# RELAIS.net
KiCad netlist of a schematic drawn in Altium Designer
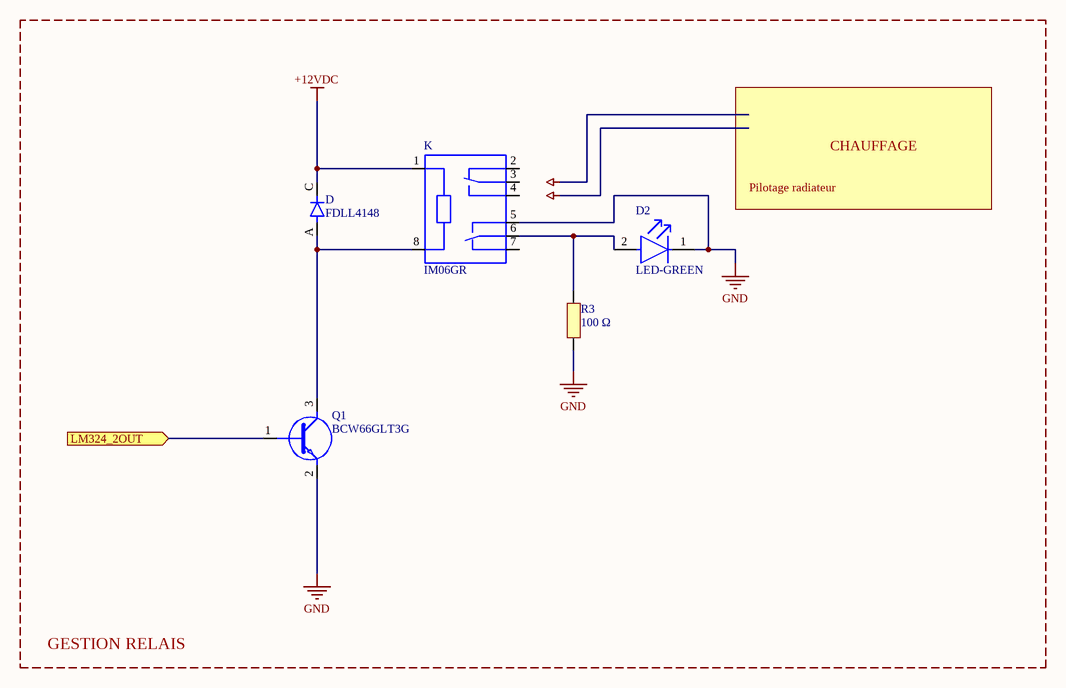
[diagram p0: RELAIS.SchDoc]

(export (version "E")
  (design (tool "Eeschema 10.0.6"))
  (components
    (comp (ref "D")
      (value "FDLL4148")
      (footprint "DIOMELF3414N")
      (description "Diode Standard 100V 200mA Surface Mount SOD-80")
      (fields (field (name "MF") "ON Semiconductor") (field (name "DIGI-KEY_PART_NUMBER") "FDLL4148CT-ND"))
      (libsource (lib "Schlib1") (part "FDLL4148"))
    )
    (comp (ref "D2")
      (value "LED-GREEN")
      (footprint "SMD-1608-LED")
      (description "LED GREEN CLEAR CHIP SMD LTST-C190GKT")
      (fields (field (name "VOLTAGE") "2V"))
      (libsource (lib "Schlib1") (part "LED-GREEN"))
    )
    (comp (ref "K")
      (value "IM06GR")
      (footprint "RELAY_IM06GR")
      (description "Electromechanical Relay 12VDC 1.029KOhm 2A DPDT _10x7.5x5.65_mm SMD Signal Relay")
      (fields (field (name "MF") "TE Connectivity"))
      (libsource (lib "Schlib1") (part "IM06GR"))
    )
    (comp (ref "Q1")
      (value "BCW66GLT3G")
      (footprint "SOT96P237X111-3N")
      (description "NPN Bipolar Transistor")
      (fields (field (name "MOUSER PART NUMBER") "863-BCW66GLT3G"))
      (libsource (lib "Schlib1") (part "BCW66GLT3G"))
    )
    (comp (ref "R3") (value "100 Ω") (footprint "RESC1005X06N") (libsource (lib "Schlib1") (part "Resistor")))
  )
  (nets
    (net (code "1") (name "+12VDC") (class "Default")
      (node (ref "D") (pin "C") (pinfunction "C_C") (pintype "passive"))
      (node (ref "K") (pin "1") (pinfunction "1_1") (pintype "passive"))
    )
    (net (code "2") (name "/LM324_2OUT") (class "Default")
      (node (ref "Q1") (pin "1") (pinfunction "B_1") (pintype "passive"))
    )
    (net (code "4") (name "GND") (class "Default")
      (node (ref "D2") (pin "1") (pinfunction "C_1") (pintype "passive"))
      (node (ref "K") (pin "5") (pinfunction "5_5") (pintype "passive"))
      (node (ref "Q1") (pin "2") (pinfunction "E_2") (pintype "passive"))
      (node (ref "R3") (pin "2") (pinfunction "2_2") (pintype "passive"))
    )
    (net (code "5") (name "Net-(D2-A)") (class "Default")
      (node (ref "D2") (pin "2") (pinfunction "A_2") (pintype "passive"))
      (node (ref "K") (pin "6") (pinfunction "6_6") (pintype "passive"))
      (node (ref "R3") (pin "1") (pinfunction "1_1") (pintype "passive"))
    )
    (net (code "6") (name "Net-(Q1-C)") (class "Default")
      (node (ref "D") (pin "A") (pinfunction "A_A") (pintype "passive"))
      (node (ref "K") (pin "8") (pinfunction "8_8") (pintype "passive"))
      (node (ref "Q1") (pin "3") (pinfunction "C_3") (pintype "passive"))
    )
    (net (code "7") (name "unconnected-(K-Pad2)") (class "Default")
      (node (ref "K") (pin "2") (pinfunction "2_2") (pintype "passive"))
    )
    (net (code "8") (name "unconnected-(K-Pad3)") (class "Default")
      (node (ref "K") (pin "3") (pinfunction "3_3") (pintype "passive"))
    )
    (net (code "9") (name "unconnected-(K-Pad4)") (class "Default")
      (node (ref "K") (pin "4") (pinfunction "4_4") (pintype "passive"))
    )
    (net (code "10") (name "unconnected-(K-Pad7)") (class "Default")
      (node (ref "K") (pin "7") (pinfunction "7_7") (pintype "passive"))
    )
  )
)
